# Board_ESP32_2Bluepill.net
KiCad netlist of a schematic drawn in EAGLE
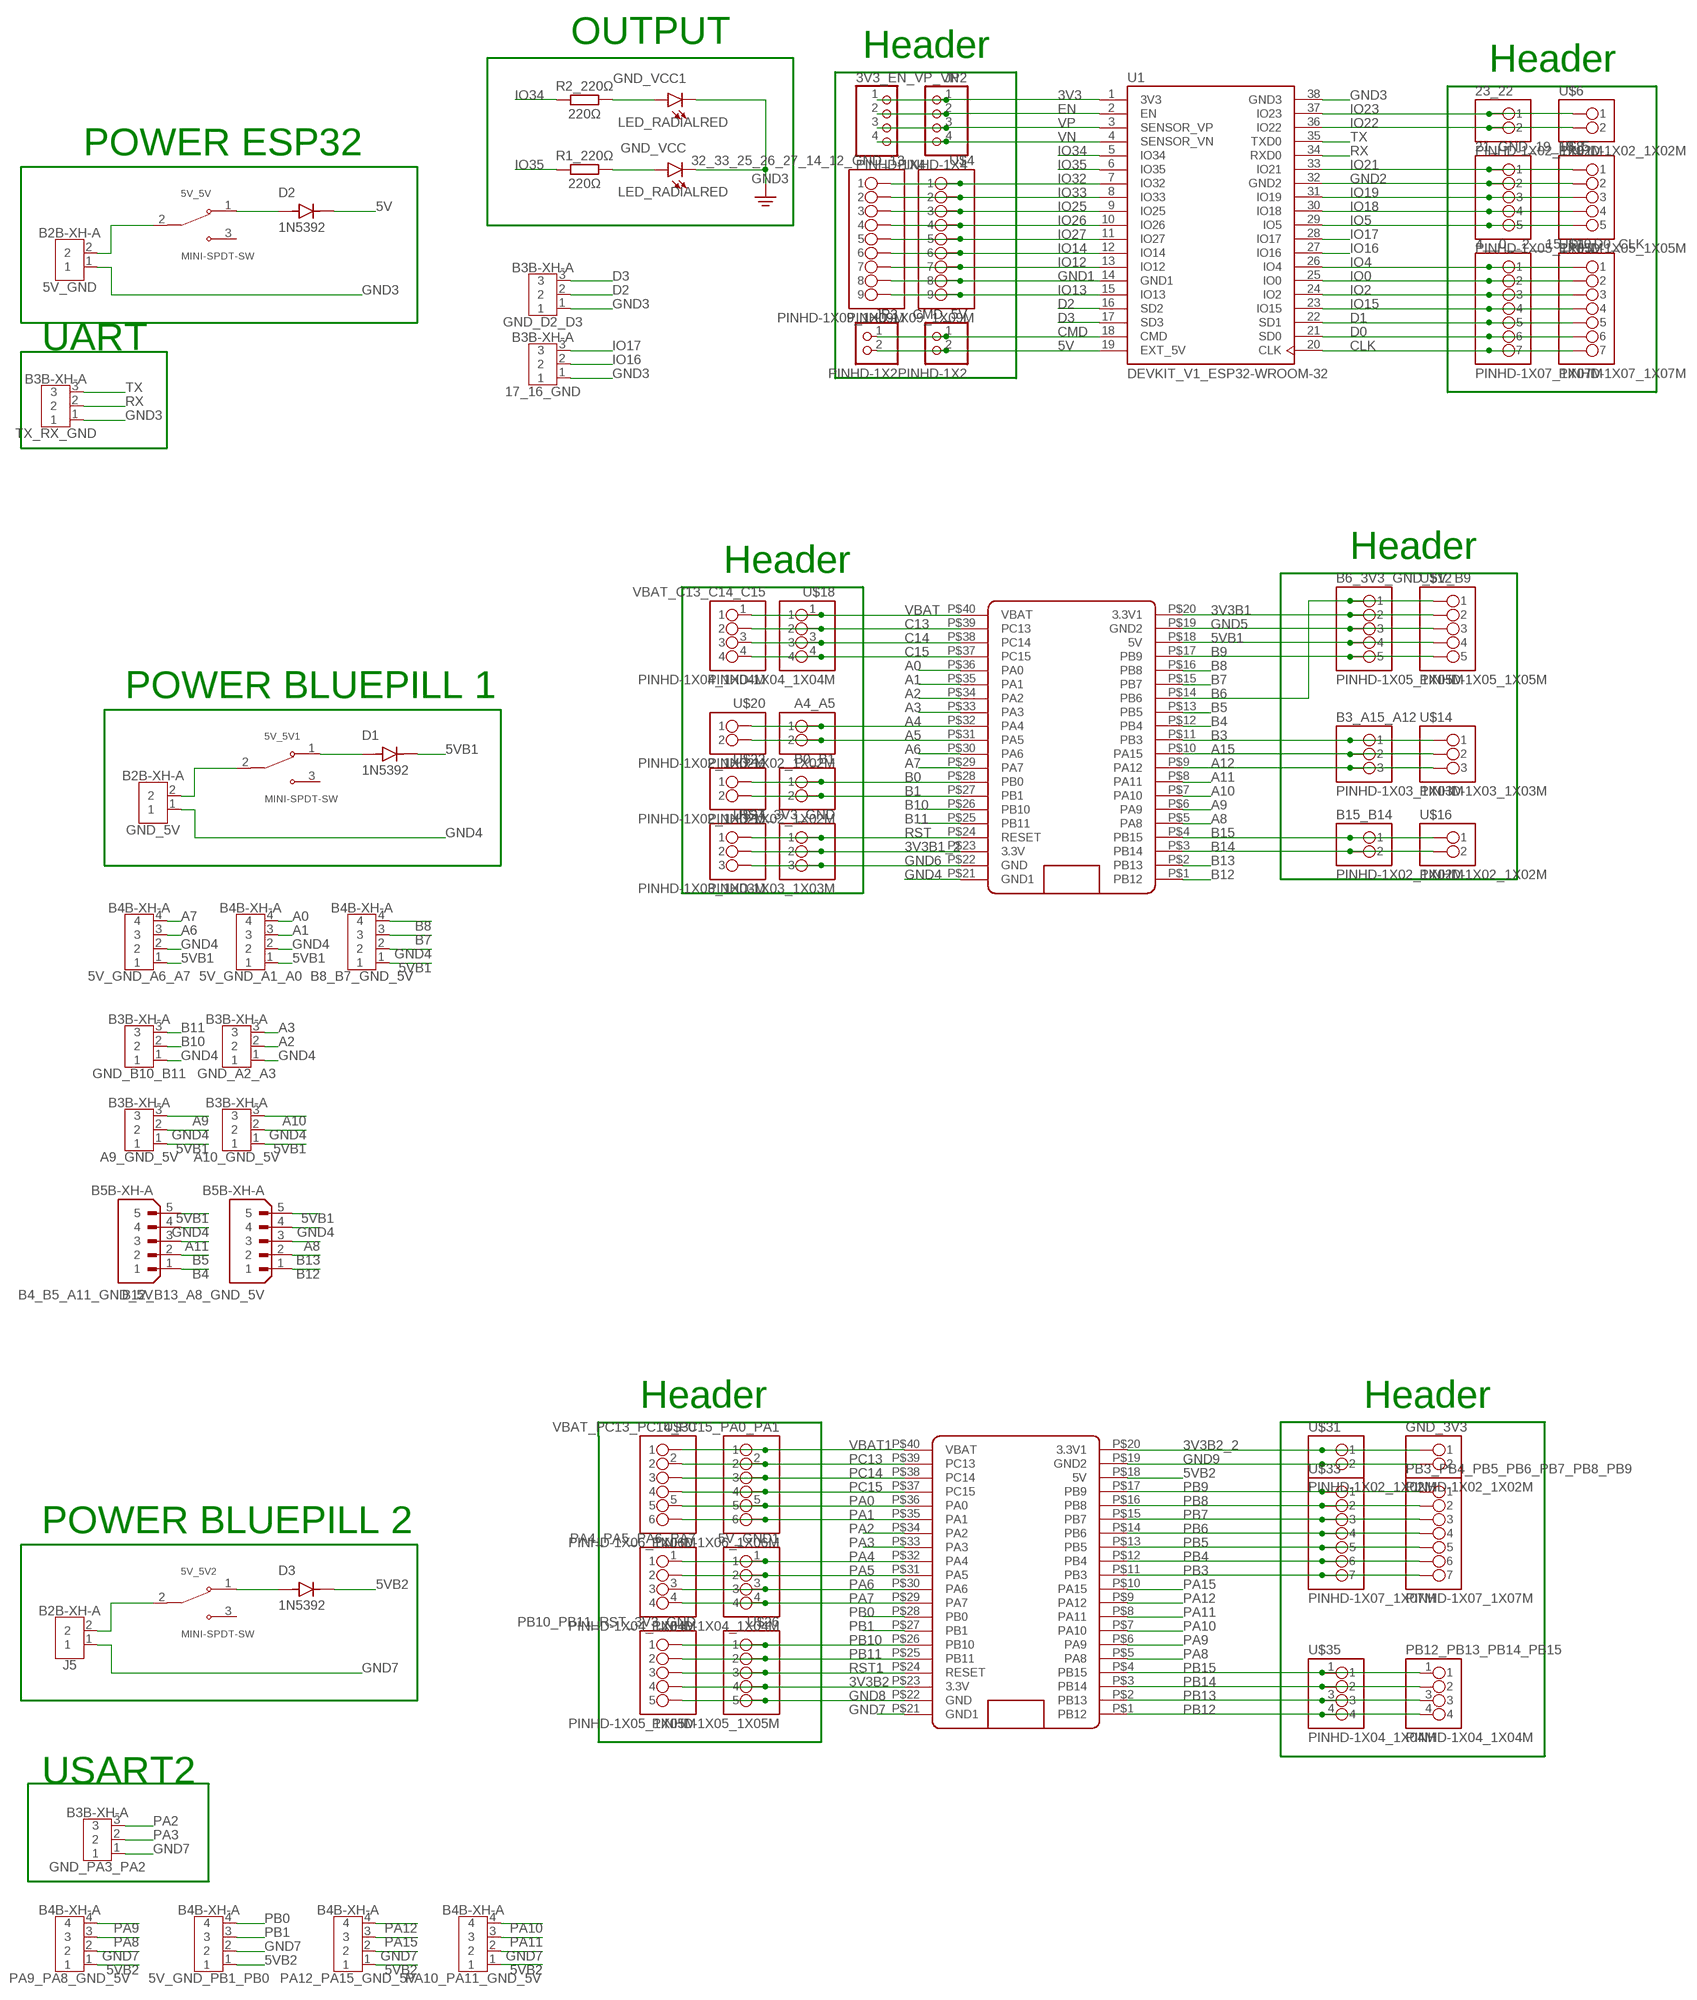
[diagram p0: schematic, sheet 1]

(export (version "E")
  (design (tool "Eeschema 10.0.6"))
  (components
    (comp (ref "3V3_EN_VP_VN")
      (value "PINHD-1X4")
      (footprint "eagle-import:1X04")
      (libsource (lib "eagle-import") (part "PINHD-1X4"))
    )
    (comp (ref "4__0__2__15_D1_D0_CLK")
      (value "PINHD-1X07_1X07M")
      (footprint "eagle-import:1X07")
      (libsource (lib "eagle-import") (part "PINHD-1X07_1X07M"))
    )
    (comp (ref "5V_5V")
      (value "MINI-SPDT-SW")
      (footprint "eagle-import:SW_MINI-SPDT-SW")
      (fields (field (name "MF") "Gravitech"))
      (libsource (lib "eagle-import") (part "MINI-SPDT-SW"))
    )
    (comp (ref "5V_5V1")
      (value "MINI-SPDT-SW")
      (footprint "eagle-import:SW_MINI-SPDT-SW")
      (fields (field (name "MF") "Gravitech"))
      (libsource (lib "eagle-import") (part "MINI-SPDT-SW"))
    )
    (comp (ref "5V_5V2")
      (value "MINI-SPDT-SW")
      (footprint "eagle-import:SW_MINI-SPDT-SW")
      (fields (field (name "MF") "Gravitech"))
      (libsource (lib "eagle-import") (part "MINI-SPDT-SW"))
    )
    (comp (ref "5V_GND")
      (value "B2B-XH-A")
      (footprint "eagle-import:B2B-XH-A")
      (fields (field (name "MANUFACTURER") "JST Sales America Inc."))
      (libsource (lib "eagle-import") (part "B2B-XH-A"))
    )
    (comp (ref "5V_GND1")
      (value "PINHD-1X04_1X04M")
      (footprint "eagle-import:1X04")
      (libsource (lib "eagle-import") (part "PINHD-1X04_1X04M"))
    )
    (comp (ref "5V_GND_A1_A0")
      (value "B4B-XH-A")
      (footprint "eagle-import:B4B-XH-A")
      (fields (field (name "MANUFACTURER") "JST Sales America Inc."))
      (libsource (lib "eagle-import") (part "B4B-XH-A"))
    )
    (comp (ref "5V_GND_A6_A7")
      (value "B4B-XH-A")
      (footprint "eagle-import:B4B-XH-A")
      (fields (field (name "MANUFACTURER") "JST Sales America Inc."))
      (libsource (lib "eagle-import") (part "B4B-XH-A"))
    )
    (comp (ref "5V_GND_PB1_PB0")
      (value "B4B-XH-A")
      (footprint "eagle-import:B4B-XH-A")
      (fields (field (name "MANUFACTURER") "JST Sales America Inc."))
      (libsource (lib "eagle-import") (part "B4B-XH-A"))
    )
    (comp (ref "17_16_GND")
      (value "B3B-XH-A")
      (footprint "eagle-import:B3B-XH-A")
      (fields (field (name "MANUFACTURER") "JST Sales America Inc."))
      (libsource (lib "eagle-import") (part "B3B-XH-A"))
    )
    (comp (ref "21_GND_19_18_5")
      (value "PINHD-1X05_1X05M")
      (footprint "eagle-import:1X05")
      (libsource (lib "eagle-import") (part "PINHD-1X05_1X05M"))
    )
    (comp (ref "23_22")
      (value "PINHD-1X02_1X02M")
      (footprint "eagle-import:1X02")
      (libsource (lib "eagle-import") (part "PINHD-1X02_1X02M"))
    )
    (comp (ref "32_33_25_26_27_14_12_GND_13")
      (value "PINHD-1X09_1X09M")
      (footprint "eagle-import:1X09")
      (libsource (lib "eagle-import") (part "PINHD-1X09_1X09M"))
    )
    (comp (ref "A4_A5")
      (value "PINHD-1X02_1X02M")
      (footprint "eagle-import:1X02")
      (libsource (lib "eagle-import") (part "PINHD-1X02_1X02M"))
    )
    (comp (ref "A9_GND_5V")
      (value "B3B-XH-A")
      (footprint "eagle-import:B3B-XH-A")
      (fields (field (name "MANUFACTURER") "JST Sales America Inc."))
      (libsource (lib "eagle-import") (part "B3B-XH-A"))
    )
    (comp (ref "A10_GND_5V")
      (value "B3B-XH-A")
      (footprint "eagle-import:B3B-XH-A")
      (fields (field (name "MANUFACTURER") "JST Sales America Inc."))
      (libsource (lib "eagle-import") (part "B3B-XH-A"))
    )
    (comp (ref "B0_B1")
      (value "PINHD-1X02_1X02M")
      (footprint "eagle-import:1X02")
      (libsource (lib "eagle-import") (part "PINHD-1X02_1X02M"))
    )
    (comp (ref "B3_A15_A12")
      (value "PINHD-1X03_1X03M")
      (footprint "eagle-import:1X03")
      (libsource (lib "eagle-import") (part "PINHD-1X03_1X03M"))
    )
    (comp (ref "B4_B5_A11_GND_5V")
      (value "B5B-XH-A")
      (footprint "eagle-import:JST_B5B-XH-A")
      (fields (field (name "MF") "JST Sales"))
      (libsource (lib "eagle-import") (part "B5B-XH-A"))
    )
    (comp (ref "B6_3V3_GND_5V_B9")
      (value "PINHD-1X05_1X05M")
      (footprint "eagle-import:1X05")
      (libsource (lib "eagle-import") (part "PINHD-1X05_1X05M"))
    )
    (comp (ref "B8_B7_GND_5V")
      (value "B4B-XH-A")
      (footprint "eagle-import:B4B-XH-A")
      (fields (field (name "MANUFACTURER") "JST Sales America Inc."))
      (libsource (lib "eagle-import") (part "B4B-XH-A"))
    )
    (comp (ref "B12_B13_A8_GND_5V")
      (value "B5B-XH-A")
      (footprint "eagle-import:JST_B5B-XH-A")
      (fields (field (name "MF") "JST Sales"))
      (libsource (lib "eagle-import") (part "B5B-XH-A"))
    )
    (comp (ref "B15_B14")
      (value "PINHD-1X02_1X02M")
      (footprint "eagle-import:1X02")
      (libsource (lib "eagle-import") (part "PINHD-1X02_1X02M"))
    )
    (comp (ref "CMD_5V")
      (value "PINHD-1X2")
      (footprint "eagle-import:1X02")
      (libsource (lib "eagle-import") (part "PINHD-1X2"))
    )
    (comp (ref "D1")
      (value "1N5392")
      (footprint "eagle-import:DIOAD1300W80L670D310")
      (fields (field (name "MF") "ON Semiconductor"))
      (libsource (lib "eagle-import") (part "1N5392"))
    )
    (comp (ref "D2")
      (value "1N5392")
      (footprint "eagle-import:DIOAD1300W80L670D310")
      (fields (field (name "MF") "ON Semiconductor"))
      (libsource (lib "eagle-import") (part "1N5392"))
    )
    (comp (ref "D3")
      (value "1N5392")
      (footprint "eagle-import:DIOAD1300W80L670D310")
      (fields (field (name "MF") "ON Semiconductor"))
      (libsource (lib "eagle-import") (part "1N5392"))
    )
    (comp (ref "GND_3V3")
      (value "PINHD-1X02_1X02M")
      (footprint "eagle-import:1X02")
      (libsource (lib "eagle-import") (part "PINHD-1X02_1X02M"))
    )
    (comp (ref "GND_5V")
      (value "B2B-XH-A")
      (footprint "eagle-import:B2B-XH-A")
      (fields (field (name "MANUFACTURER") "JST Sales America Inc."))
      (libsource (lib "eagle-import") (part "B2B-XH-A"))
    )
    (comp (ref "GND_A2_A3")
      (value "B3B-XH-A")
      (footprint "eagle-import:B3B-XH-A")
      (fields (field (name "MANUFACTURER") "JST Sales America Inc."))
      (libsource (lib "eagle-import") (part "B3B-XH-A"))
    )
    (comp (ref "GND_B10_B11")
      (value "B3B-XH-A")
      (footprint "eagle-import:B3B-XH-A")
      (fields (field (name "MANUFACTURER") "JST Sales America Inc."))
      (libsource (lib "eagle-import") (part "B3B-XH-A"))
    )
    (comp (ref "GND_D2_D3")
      (value "B3B-XH-A")
      (footprint "eagle-import:B3B-XH-A")
      (fields (field (name "MANUFACTURER") "JST Sales America Inc."))
      (libsource (lib "eagle-import") (part "B3B-XH-A"))
    )
    (comp (ref "GND_PA3_PA2")
      (value "B3B-XH-A")
      (footprint "eagle-import:B3B-XH-A")
      (fields (field (name "MANUFACTURER") "JST Sales America Inc."))
      (libsource (lib "eagle-import") (part "B3B-XH-A"))
    )
    (comp (ref "GND_VCC")
      (value "LED_RADIALRED")
      (footprint "eagle-import:LEDRD254W60D565H860B_R")
      (libsource (lib "eagle-import") (part "LED_RADIALRED"))
    )
    (comp (ref "GND_VCC1")
      (value "LED_RADIALRED")
      (footprint "eagle-import:LEDRD254W60D565H860B_R")
      (libsource (lib "eagle-import") (part "LED_RADIALRED"))
    )
    (comp (ref "J5")
      (value "B2B-XH-A")
      (footprint "eagle-import:B2B-XH-A")
      (fields (field (name "MANUFACTURER") "JST Sales America Inc."))
      (libsource (lib "eagle-import") (part "B2B-XH-A"))
    )
    (comp (ref "JP2")
      (value "PINHD-1X4")
      (footprint "eagle-import:1X04")
      (libsource (lib "eagle-import") (part "PINHD-1X4"))
    )
    (comp (ref "JP3")
      (value "PINHD-1X2")
      (footprint "eagle-import:1X02")
      (libsource (lib "eagle-import") (part "PINHD-1X2"))
    )
    (comp (ref "PA4_PA5_PA6_PA7")
      (value "PINHD-1X04_1X04M")
      (footprint "eagle-import:1X04")
      (libsource (lib "eagle-import") (part "PINHD-1X04_1X04M"))
    )
    (comp (ref "PA9_PA8_GND_5V")
      (value "B4B-XH-A")
      (footprint "eagle-import:B4B-XH-A")
      (fields (field (name "MANUFACTURER") "JST Sales America Inc."))
      (libsource (lib "eagle-import") (part "B4B-XH-A"))
    )
    (comp (ref "PA10_PA11_GND_5V")
      (value "B4B-XH-A")
      (footprint "eagle-import:B4B-XH-A")
      (fields (field (name "MANUFACTURER") "JST Sales America Inc."))
      (libsource (lib "eagle-import") (part "B4B-XH-A"))
    )
    (comp (ref "PA12_PA15_GND_5V")
      (value "B4B-XH-A")
      (footprint "eagle-import:B4B-XH-A")
      (fields (field (name "MANUFACTURER") "JST Sales America Inc."))
      (libsource (lib "eagle-import") (part "B4B-XH-A"))
    )
    (comp (ref "PB3_PB4_PB5_PB6_PB7_PB8_PB9")
      (value "PINHD-1X07_1X07M")
      (footprint "eagle-import:1X07")
      (libsource (lib "eagle-import") (part "PINHD-1X07_1X07M"))
    )
    (comp (ref "PB10_PB11_RST_3V3_GND")
      (value "PINHD-1X05_1X05M")
      (footprint "eagle-import:1X05")
      (libsource (lib "eagle-import") (part "PINHD-1X05_1X05M"))
    )
    (comp (ref "PB12_PB13_PB14_PB15")
      (value "PINHD-1X04_1X04M")
      (footprint "eagle-import:1X04")
      (libsource (lib "eagle-import") (part "PINHD-1X04_1X04M"))
    )
    (comp (ref "R1_220Ω")
      (value "220Ω")
      (footprint "eagle-import:RESAD1176W63L850D250B")
      (libsource (lib "eagle-import") (part "RAXIAL-11.7MM-PITCH_"))
    )
    (comp (ref "R2_220Ω")
      (value "220Ω")
      (footprint "eagle-import:RESAD1176W63L850D250B")
      (libsource (lib "eagle-import") (part "RAXIAL-11.7MM-PITCH_"))
    )
    (comp (ref "RST_3V3_GND")
      (value "PINHD-1X03_1X03M")
      (footprint "eagle-import:1X03")
      (libsource (lib "eagle-import") (part "PINHD-1X03_1X03M"))
    )
    (comp (ref "TX_RX_GND")
      (value "B3B-XH-A")
      (footprint "eagle-import:B3B-XH-A")
      (fields (field (name "MANUFACTURER") "JST Sales America Inc."))
      (libsource (lib "eagle-import") (part "B3B-XH-A"))
    )
    (comp (ref "U$1")
      (value "BLUE_PILL")
      (footprint "eagle-import:BLUE_PILL")
      (libsource (lib "eagle-import") (part "BLUE_PILL"))
    )
    (comp (ref "U$2")
      (value "BLUE_PILL")
      (footprint "eagle-import:BLUE_PILL")
      (libsource (lib "eagle-import") (part "BLUE_PILL"))
    )
    (comp (ref "U$4")
      (value "PINHD-1X09_1X09M")
      (footprint "eagle-import:1X09")
      (libsource (lib "eagle-import") (part "PINHD-1X09_1X09M"))
    )
    (comp (ref "U$6")
      (value "PINHD-1X02_1X02M")
      (footprint "eagle-import:1X02")
      (libsource (lib "eagle-import") (part "PINHD-1X02_1X02M"))
    )
    (comp (ref "U$8")
      (value "PINHD-1X05_1X05M")
      (footprint "eagle-import:1X05")
      (libsource (lib "eagle-import") (part "PINHD-1X05_1X05M"))
    )
    (comp (ref "U$10")
      (value "PINHD-1X07_1X07M")
      (footprint "eagle-import:1X07")
      (libsource (lib "eagle-import") (part "PINHD-1X07_1X07M"))
    )
    (comp (ref "U$12")
      (value "PINHD-1X05_1X05M")
      (footprint "eagle-import:1X05")
      (libsource (lib "eagle-import") (part "PINHD-1X05_1X05M"))
    )
    (comp (ref "U$14")
      (value "PINHD-1X03_1X03M")
      (footprint "eagle-import:1X03")
      (libsource (lib "eagle-import") (part "PINHD-1X03_1X03M"))
    )
    (comp (ref "U$16")
      (value "PINHD-1X02_1X02M")
      (footprint "eagle-import:1X02")
      (libsource (lib "eagle-import") (part "PINHD-1X02_1X02M"))
    )
    (comp (ref "U$18")
      (value "PINHD-1X04_1X04M")
      (footprint "eagle-import:1X04")
      (libsource (lib "eagle-import") (part "PINHD-1X04_1X04M"))
    )
    (comp (ref "U$20")
      (value "PINHD-1X02_1X02M")
      (footprint "eagle-import:1X02")
      (libsource (lib "eagle-import") (part "PINHD-1X02_1X02M"))
    )
    (comp (ref "U$22")
      (value "PINHD-1X02_1X02M")
      (footprint "eagle-import:1X02")
      (libsource (lib "eagle-import") (part "PINHD-1X02_1X02M"))
    )
    (comp (ref "U$24")
      (value "PINHD-1X03_1X03M")
      (footprint "eagle-import:1X03")
      (libsource (lib "eagle-import") (part "PINHD-1X03_1X03M"))
    )
    (comp (ref "U$26")
      (value "PINHD-1X05_1X05M")
      (footprint "eagle-import:1X05")
      (libsource (lib "eagle-import") (part "PINHD-1X05_1X05M"))
    )
    (comp (ref "U$30")
      (value "PINHD-1X06_1X06M")
      (footprint "eagle-import:1X06")
      (libsource (lib "eagle-import") (part "PINHD-1X06_1X06M"))
    )
    (comp (ref "U$31")
      (value "PINHD-1X02_1X02M")
      (footprint "eagle-import:1X02")
      (libsource (lib "eagle-import") (part "PINHD-1X02_1X02M"))
    )
    (comp (ref "U$33")
      (value "PINHD-1X07_1X07M")
      (footprint "eagle-import:1X07")
      (libsource (lib "eagle-import") (part "PINHD-1X07_1X07M"))
    )
    (comp (ref "U$35")
      (value "PINHD-1X04_1X04M")
      (footprint "eagle-import:1X04")
      (libsource (lib "eagle-import") (part "PINHD-1X04_1X04M"))
    )
    (comp (ref "U1")
      (value "DEVKIT_V1_ESP32-WROOM-32")
      (footprint "eagle-import:MODULE_DEVKIT_V1_ESP32-WROOM-32")
      (fields (field (name "MF") "Espressif Systems") (field (name "MP") "DEVKIT V1 ESP32-WROOM-32"))
      (libsource (lib "eagle-import") (part "DEVKIT_V1_ESP32-WROOM-32"))
    )
    (comp (ref "VBAT_C13_C14_C15")
      (value "PINHD-1X04_1X04M")
      (footprint "eagle-import:1X04")
      (libsource (lib "eagle-import") (part "PINHD-1X04_1X04M"))
    )
    (comp (ref "VBAT_PC13_PC14_PC15_PA0_PA1")
      (value "PINHD-1X06_1X06M")
      (footprint "eagle-import:1X06")
      (libsource (lib "eagle-import") (part "PINHD-1X06_1X06M"))
    )
  )
  (nets
    (net (code "1") (name "/3V3") (class "Default")
      (node (ref "3V3_EN_VP_VN") (pin "1") (pinfunction "1_1") (pintype "passive"))
      (node (ref "JP2") (pin "1") (pinfunction "1_1") (pintype "passive"))
      (node (ref "U1") (pin "1") (pinfunction "3V3_1") (pintype "power_in"))
    )
    (net (code "2") (name "/3V3B1") (class "Default")
      (node (ref "B6_3V3_GND_5V_B9") (pin "2") (pinfunction "2_2") (pintype "bidirectional"))
      (node (ref "U$1") (pin "P$20") (pinfunction "3.3V1_P$20") (pintype "bidirectional"))
      (node (ref "U$12") (pin "2") (pinfunction "2_2") (pintype "bidirectional"))
    )
    (net (code "3") (name "/3V3B1_2") (class "Default")
      (node (ref "RST_3V3_GND") (pin "2") (pinfunction "2_2") (pintype "bidirectional"))
      (node (ref "U$1") (pin "P$23") (pinfunction "3.3V_P$23") (pintype "bidirectional"))
      (node (ref "U$24") (pin "2") (pinfunction "2_2") (pintype "bidirectional"))
    )
    (net (code "4") (name "/3V3B2") (class "Default")
      (node (ref "PB10_PB11_RST_3V3_GND") (pin "4") (pinfunction "4_4") (pintype "bidirectional"))
      (node (ref "U$2") (pin "P$23") (pinfunction "3.3V_P$23") (pintype "bidirectional"))
      (node (ref "U$26") (pin "4") (pinfunction "4_4") (pintype "bidirectional"))
    )
    (net (code "5") (name "/3V3B2_2") (class "Default")
      (node (ref "GND_3V3") (pin "1") (pinfunction "1_1") (pintype "bidirectional"))
      (node (ref "U$2") (pin "P$20") (pinfunction "3.3V1_P$20") (pintype "bidirectional"))
      (node (ref "U$31") (pin "1") (pinfunction "1_1") (pintype "bidirectional"))
    )
    (net (code "6") (name "/5V") (class "Default")
      (node (ref "CMD_5V") (pin "2") (pinfunction "2_2") (pintype "passive"))
      (node (ref "D2") (pin "C") (pinfunction "K_C") (pintype "passive"))
      (node (ref "JP3") (pin "2") (pinfunction "2_2") (pintype "passive"))
      (node (ref "U1") (pin "19") (pinfunction "EXT_5V_19") (pintype "power_in"))
    )
    (net (code "7") (name "/5VB1") (class "Default")
      (node (ref "5V_GND_A1_A0") (pin "1") (pinfunction "1_1") (pintype "bidirectional"))
      (node (ref "5V_GND_A6_A7") (pin "1") (pinfunction "1_1") (pintype "bidirectional"))
      (node (ref "A10_GND_5V") (pin "1") (pinfunction "1_1") (pintype "bidirectional"))
      (node (ref "A9_GND_5V") (pin "1") (pinfunction "1_1") (pintype "bidirectional"))
      (node (ref "B12_B13_A8_GND_5V") (pin "5") (pinfunction "5_5") (pintype "passive"))
      (node (ref "B4_B5_A11_GND_5V") (pin "5") (pinfunction "5_5") (pintype "passive"))
      (node (ref "B6_3V3_GND_5V_B9") (pin "4") (pinfunction "4_4") (pintype "bidirectional"))
      (node (ref "B8_B7_GND_5V") (pin "1") (pinfunction "1_1") (pintype "bidirectional"))
      (node (ref "D1") (pin "C") (pinfunction "K_C") (pintype "passive"))
      (node (ref "U$1") (pin "P$18") (pinfunction "5V_P$18") (pintype "bidirectional"))
      (node (ref "U$12") (pin "4") (pinfunction "4_4") (pintype "bidirectional"))
    )
    (net (code "8") (name "/5VB2") (class "Default")
      (node (ref "5V_GND_PB1_PB0") (pin "1") (pinfunction "1_1") (pintype "bidirectional"))
      (node (ref "D3") (pin "C") (pinfunction "K_C") (pintype "passive"))
      (node (ref "PA10_PA11_GND_5V") (pin "1") (pinfunction "1_1") (pintype "bidirectional"))
      (node (ref "PA12_PA15_GND_5V") (pin "1") (pinfunction "1_1") (pintype "bidirectional"))
      (node (ref "PA9_PA8_GND_5V") (pin "1") (pinfunction "1_1") (pintype "bidirectional"))
      (node (ref "U$2") (pin "P$18") (pinfunction "5V_P$18") (pintype "bidirectional"))
    )
    (net (code "9") (name "/A0") (class "Default")
      (node (ref "5V_GND_A1_A0") (pin "4") (pinfunction "4_4") (pintype "bidirectional"))
      (node (ref "U$1") (pin "P$36") (pinfunction "PA0_P$36") (pintype "bidirectional"))
    )
    (net (code "10") (name "/A1") (class "Default")
      (node (ref "5V_GND_A1_A0") (pin "3") (pinfunction "3_3") (pintype "bidirectional"))
      (node (ref "U$1") (pin "P$35") (pinfunction "PA1_P$35") (pintype "bidirectional"))
    )
    (net (code "11") (name "/A2") (class "Default")
      (node (ref "GND_A2_A3") (pin "2") (pinfunction "2_2") (pintype "bidirectional"))
      (node (ref "U$1") (pin "P$34") (pinfunction "PA2_P$34") (pintype "bidirectional"))
    )
    (net (code "12") (name "/A3") (class "Default")
      (node (ref "GND_A2_A3") (pin "3") (pinfunction "3_3") (pintype "bidirectional"))
      (node (ref "U$1") (pin "P$33") (pinfunction "PA3_P$33") (pintype "bidirectional"))
    )
    (net (code "13") (name "/A4") (class "Default")
      (node (ref "A4_A5") (pin "1") (pinfunction "1_1") (pintype "bidirectional"))
      (node (ref "U$1") (pin "P$32") (pinfunction "PA4_P$32") (pintype "bidirectional"))
      (node (ref "U$20") (pin "1") (pinfunction "1_1") (pintype "bidirectional"))
    )
    (net (code "14") (name "/A5") (class "Default")
      (node (ref "A4_A5") (pin "2") (pinfunction "2_2") (pintype "bidirectional"))
      (node (ref "U$1") (pin "P$31") (pinfunction "PA5_P$31") (pintype "bidirectional"))
      (node (ref "U$20") (pin "2") (pinfunction "2_2") (pintype "bidirectional"))
    )
    (net (code "15") (name "/A6") (class "Default")
      (node (ref "5V_GND_A6_A7") (pin "3") (pinfunction "3_3") (pintype "bidirectional"))
      (node (ref "U$1") (pin "P$30") (pinfunction "PA6_P$30") (pintype "bidirectional"))
    )
    (net (code "16") (name "/A7") (class "Default")
      (node (ref "5V_GND_A6_A7") (pin "4") (pinfunction "4_4") (pintype "bidirectional"))
      (node (ref "U$1") (pin "P$29") (pinfunction "PA7_P$29") (pintype "bidirectional"))
    )
    (net (code "17") (name "/A8") (class "Default")
      (node (ref "B12_B13_A8_GND_5V") (pin "3") (pinfunction "3_3") (pintype "passive"))
      (node (ref "U$1") (pin "P$5") (pinfunction "PA8_P$5") (pintype "bidirectional"))
    )
    (net (code "18") (name "/A9") (class "Default")
      (node (ref "A9_GND_5V") (pin "3") (pinfunction "3_3") (pintype "bidirectional"))
      (node (ref "U$1") (pin "P$6") (pinfunction "PA9_P$6") (pintype "bidirectional"))
    )
    (net (code "19") (name "/A10") (class "Default")
      (node (ref "A10_GND_5V") (pin "3") (pinfunction "3_3") (pintype "bidirectional"))
      (node (ref "U$1") (pin "P$7") (pinfunction "PA10_P$7") (pintype "bidirectional"))
    )
    (net (code "20") (name "/A11") (class "Default")
      (node (ref "B4_B5_A11_GND_5V") (pin "3") (pinfunction "3_3") (pintype "passive"))
      (node (ref "U$1") (pin "P$8") (pinfunction "PA11_P$8") (pintype "bidirectional"))
    )
    (net (code "21") (name "/A12") (class "Default")
      (node (ref "B3_A15_A12") (pin "3") (pinfunction "3_3") (pintype "bidirectional"))
      (node (ref "U$1") (pin "P$9") (pinfunction "PA12_P$9") (pintype "bidirectional"))
      (node (ref "U$14") (pin "3") (pinfunction "3_3") (pintype "bidirectional"))
    )
    (net (code "22") (name "/A15") (class "Default")
      (node (ref "B3_A15_A12") (pin "2") (pinfunction "2_2") (pintype "bidirectional"))
      (node (ref "U$1") (pin "P$10") (pinfunction "PA15_P$10") (pintype "bidirectional"))
      (node (ref "U$14") (pin "2") (pinfunction "2_2") (pintype "bidirectional"))
    )
    (net (code "23") (name "/B0") (class "Default")
      (node (ref "B0_B1") (pin "1") (pinfunction "1_1") (pintype "bidirectional"))
      (node (ref "U$1") (pin "P$28") (pinfunction "PB0_P$28") (pintype "bidirectional"))
      (node (ref "U$22") (pin "1") (pinfunction "1_1") (pintype "bidirectional"))
    )
    (net (code "24") (name "/B1") (class "Default")
      (node (ref "B0_B1") (pin "2") (pinfunction "2_2") (pintype "bidirectional"))
      (node (ref "U$1") (pin "P$27") (pinfunction "PB1_P$27") (pintype "bidirectional"))
      (node (ref "U$22") (pin "2") (pinfunction "2_2") (pintype "bidirectional"))
    )
    (net (code "25") (name "/B3") (class "Default")
      (node (ref "B3_A15_A12") (pin "1") (pinfunction "1_1") (pintype "bidirectional"))
      (node (ref "U$1") (pin "P$11") (pinfunction "PB3_P$11") (pintype "bidirectional"))
      (node (ref "U$14") (pin "1") (pinfunction "1_1") (pintype "bidirectional"))
    )
    (net (code "26") (name "/B4") (class "Default")
      (node (ref "B4_B5_A11_GND_5V") (pin "1") (pinfunction "1_1") (pintype "passive"))
      (node (ref "U$1") (pin "P$12") (pinfunction "PB4_P$12") (pintype "bidirectional"))
    )
    (net (code "27") (name "/B5") (class "Default")
      (node (ref "B4_B5_A11_GND_5V") (pin "2") (pinfunction "2_2") (pintype "passive"))
      (node (ref "U$1") (pin "P$13") (pinfunction "PB5_P$13") (pintype "bidirectional"))
    )
    (net (code "28") (name "/B6") (class "Default")
      (node (ref "B6_3V3_GND_5V_B9") (pin "1") (pinfunction "1_1") (pintype "bidirectional"))
      (node (ref "U$1") (pin "P$14") (pinfunction "PB6_P$14") (pintype "bidirectional"))
      (node (ref "U$12") (pin "1") (pinfunction "1_1") (pintype "bidirectional"))
    )
    (net (code "29") (name "/B7") (class "Default")
      (node (ref "B8_B7_GND_5V") (pin "3") (pinfunction "3_3") (pintype "bidirectional"))
      (node (ref "U$1") (pin "P$15") (pinfunction "PB7_P$15") (pintype "bidirectional"))
    )
    (net (code "30") (name "/B8") (class "Default")
      (node (ref "B8_B7_GND_5V") (pin "4") (pinfunction "4_4") (pintype "bidirectional"))
      (node (ref "U$1") (pin "P$16") (pinfunction "PB8_P$16") (pintype "bidirectional"))
    )
    (net (code "31") (name "/B9") (class "Default")
      (node (ref "B6_3V3_GND_5V_B9") (pin "5") (pinfunction "5_5") (pintype "bidirectional"))
      (node (ref "U$1") (pin "P$17") (pinfunction "PB9_P$17") (pintype "bidirectional"))
      (node (ref "U$12") (pin "5") (pinfunction "5_5") (pintype "bidirectional"))
    )
    (net (code "32") (name "/B10") (class "Default")
      (node (ref "GND_B10_B11") (pin "2") (pinfunction "2_2") (pintype "bidirectional"))
      (node (ref "U$1") (pin "P$26") (pinfunction "PB10_P$26") (pintype "bidirectional"))
    )
    (net (code "33") (name "/B11") (class "Default")
      (node (ref "GND_B10_B11") (pin "3") (pinfunction "3_3") (pintype "bidirectional"))
      (node (ref "U$1") (pin "P$25") (pinfunction "PB11_P$25") (pintype "bidirectional"))
    )
    (net (code "34") (name "/B12") (class "Default")
      (node (ref "B12_B13_A8_GND_5V") (pin "1") (pinfunction "1_1") (pintype "passive"))
      (node (ref "U$1") (pin "P$1") (pinfunction "PB12_P$1") (pintype "bidirectional"))
    )
    (net (code "35") (name "/B13") (class "Default")
      (node (ref "B12_B13_A8_GND_5V") (pin "2") (pinfunction "2_2") (pintype "passive"))
      (node (ref "U$1") (pin "P$2") (pinfunction "PB13_P$2") (pintype "bidirectional"))
    )
    (net (code "36") (name "/B14") (class "Default")
      (node (ref "B15_B14") (pin "2") (pinfunction "2_2") (pintype "bidirectional"))
      (node (ref "U$1") (pin "P$3") (pinfunction "PB14_P$3") (pintype "bidirectional"))
      (node (ref "U$16") (pin "2") (pinfunction "2_2") (pintype "bidirectional"))
    )
    (net (code "37") (name "/B15") (class "Default")
      (node (ref "B15_B14") (pin "1") (pinfunction "1_1") (pintype "bidirectional"))
      (node (ref "U$1") (pin "P$4") (pinfunction "PB15_P$4") (pintype "bidirectional"))
      (node (ref "U$16") (pin "1") (pinfunction "1_1") (pintype "bidirectional"))
    )
    (net (code "38") (name "/C13") (class "Default")
      (node (ref "U$1") (pin "P$39") (pinfunction "PC13_P$39") (pintype "bidirectional"))
      (node (ref "U$18") (pin "2") (pinfunction "2_2") (pintype "bidirectional"))
      (node (ref "VBAT_C13_C14_C15") (pin "2") (pinfunction "2_2") (pintype "bidirectional"))
    )
    (net (code "39") (name "/C14") (class "Default")
      (node (ref "U$1") (pin "P$38") (pinfunction "PC14_P$38") (pintype "bidirectional"))
      (node (ref "U$18") (pin "3") (pinfunction "3_3") (pintype "bidirectional"))
      (node (ref "VBAT_C13_C14_C15") (pin "3") (pinfunction "3_3") (pintype "bidirectional"))
    )
    (net (code "40") (name "/C15") (class "Default")
      (node (ref "U$1") (pin "P$37") (pinfunction "PC15_P$37") (pintype "bidirectional"))
      (node (ref "U$18") (pin "4") (pinfunction "4_4") (pintype "bidirectional"))
      (node (ref "VBAT_C13_C14_C15") (pin "4") (pinfunction "4_4") (pintype "bidirectional"))
    )
    (net (code "41") (name "/CLK") (class "Default")
      (node (ref "4__0__2__15_D1_D0_CLK") (pin "7") (pinfunction "7_7") (pintype "bidirectional"))
      (node (ref "U$10") (pin "7") (pinfunction "7_7") (pintype "bidirectional"))
      (node (ref "U1") (pin "20") (pinfunction "CLK_20") (pintype "input"))
    )
    (net (code "42") (name "/CMD") (class "Default")
      (node (ref "CMD_5V") (pin "1") (pinfunction "1_1") (pintype "passive"))
      (node (ref "JP3") (pin "1") (pinfunction "1_1") (pintype "passive"))
      (node (ref "U1") (pin "18") (pinfunction "CMD_18") (pintype "bidirectional"))
    )
    (net (code "43") (name "/D0") (class "Default")
      (node (ref "4__0__2__15_D1_D0_CLK") (pin "6") (pinfunction "6_6") (pintype "bidirectional"))
      (node (ref "U$10") (pin "6") (pinfunction "6_6") (pintype "bidirectional"))
      (node (ref "U1") (pin "21") (pinfunction "SD0_21") (pintype "bidirectional"))
    )
    (net (code "44") (name "/D1") (class "Default")
      (node (ref "4__0__2__15_D1_D0_CLK") (pin "5") (pinfunction "5_5") (pintype "bidirectional"))
      (node (ref "U$10") (pin "5") (pinfunction "5_5") (pintype "bidirectional"))
      (node (ref "U1") (pin "22") (pinfunction "SD1_22") (pintype "bidirectional"))
    )
    (net (code "45") (name "/D2") (class "Default")
      (node (ref "GND_D2_D3") (pin "2") (pinfunction "2_2") (pintype "bidirectional"))
      (node (ref "U1") (pin "16") (pinfunction "SD2_16") (pintype "bidirectional"))
    )
    (net (code "46") (name "/D3") (class "Default")
      (node (ref "GND_D2_D3") (pin "3") (pinfunction "3_3") (pintype "bidirectional"))
      (node (ref "U1") (pin "17") (pinfunction "SD3_17") (pintype "bidirectional"))
    )
    (net (code "47") (name "/EN") (class "Default")
      (node (ref "3V3_EN_VP_VN") (pin "2") (pinfunction "2_2") (pintype "passive"))
      (node (ref "JP2") (pin "2") (pinfunction "2_2") (pintype "passive"))
      (node (ref "U1") (pin "2") (pinfunction "EN_2") (pintype "input"))
    )
    (net (code "48") (name "/GND1") (class "Default")
      (node (ref "32_33_25_26_27_14_12_GND_13") (pin "8") (pinfunction "8_8") (pintype "bidirectional"))
      (node (ref "U$4") (pin "8") (pinfunction "8_8") (pintype "bidirectional"))
      (node (ref "U1") (pin "14") (pinfunction "GND1_14") (pintype "power_in"))
    )
    (net (code "49") (name "/GND2") (class "Default")
      (node (ref "21_GND_19_18_5") (pin "2") (pinfunction "2_2") (pintype "bidirectional"))
      (node (ref "U$8") (pin "2") (pinfunction "2_2") (pintype "bidirectional"))
      (node (ref "U1") (pin "32") (pinfunction "GND2_32") (pintype "power_in"))
    )
    (net (code "50") (name "/GND4") (class "Default")
      (node (ref "5V_GND_A1_A0") (pin "2") (pinfunction "2_2") (pintype "bidirectional"))
      (node (ref "5V_GND_A6_A7") (pin "2") (pinfunction "2_2") (pintype "bidirectional"))
      (node (ref "A10_GND_5V") (pin "2") (pinfunction "2_2") (pintype "bidirectional"))
      (node (ref "A9_GND_5V") (pin "2") (pinfunction "2_2") (pintype "bidirectional"))
      (node (ref "B12_B13_A8_GND_5V") (pin "4") (pinfunction "4_4") (pintype "passive"))
      (node (ref "B4_B5_A11_GND_5V") (pin "4") (pinfunction "4_4") (pintype "passive"))
      (node (ref "B8_B7_GND_5V") (pin "2") (pinfunction "2_2") (pintype "bidirectional"))
      (node (ref "GND_5V") (pin "1") (pinfunction "1_1") (pintype "bidirectional"))
      (node (ref "GND_A2_A3") (pin "1") (pinfunction "1_1") (pintype "bidirectional"))
      (node (ref "GND_B10_B11") (pin "1") (pinfunction "1_1") (pintype "bidirectional"))
      (node (ref "U$1") (pin "P$21") (pinfunction "GND1_P$21") (pintype "power_in"))
    )
    (net (code "51") (name "/GND5") (class "Default")
      (node (ref "B6_3V3_GND_5V_B9") (pin "3") (pinfunction "3_3") (pintype "bidirectional"))
      (node (ref "U$1") (pin "P$19") (pinfunction "GND2_P$19") (pintype "bidirectional"))
      (node (ref "U$12") (pin "3") (pinfunction "3_3") (pintype "bidirectional"))
    )
    (net (code "52") (name "/GND6") (class "Default")
      (node (ref "RST_3V3_GND") (pin "3") (pinfunction "3_3") (pintype "bidirectional"))
      (node (ref "U$1") (pin "P$22") (pinfunction "GND_P$22") (pintype "bidirectional"))
      (node (ref "U$24") (pin "3") (pinfunction "3_3") (pintype "bidirectional"))
    )
    (net (code "53") (name "/GND7") (class "Default")
      (node (ref "5V_GND_PB1_PB0") (pin "2") (pinfunction "2_2") (pintype "bidirectional"))
      (node (ref "GND_PA3_PA2") (pin "1") (pinfunction "1_1") (pintype "bidirectional"))
      (node (ref "J5") (pin "1") (pinfunction "1_1") (pintype "bidirectional"))
      (node (ref "PA10_PA11_GND_5V") (pin "2") (pinfunction "2_2") (pintype "bidirectional"))
      (node (ref "PA12_PA15_GND_5V") (pin "2") (pinfunction "2_2") (pintype "bidirectional"))
      (node (ref "PA9_PA8_GND_5V") (pin "2") (pinfunction "2_2") (pintype "bidirectional"))
      (node (ref "U$2") (pin "P$21") (pinfunction "GND1_P$21") (pintype "power_in"))
    )
    (net (code "54") (name "/GND8") (class "Default")
      (node (ref "PB10_PB11_RST_3V3_GND") (pin "5") (pinfunction "5_5") (pintype "bidirectional"))
      (node (ref "U$2") (pin "P$22") (pinfunction "GND_P$22") (pintype "bidirectional"))
      (node (ref "U$26") (pin "5") (pinfunction "5_5") (pintype "bidirectional"))
    )
    (net (code "55") (name "/GND9") (class "Default")
      (node (ref "GND_3V3") (pin "2") (pinfunction "2_2") (pintype "bidirectional"))
      (node (ref "U$2") (pin "P$19") (pinfunction "GND2_P$19") (pintype "bidirectional"))
      (node (ref "U$31") (pin "2") (pinfunction "2_2") (pintype "bidirectional"))
    )
    (net (code "56") (name "/IO0") (class "Default")
      (node (ref "4__0__2__15_D1_D0_CLK") (pin "2") (pinfunction "2_2") (pintype "bidirectional"))
      (node (ref "U$10") (pin "2") (pinfunction "2_2") (pintype "bidirectional"))
      (node (ref "U1") (pin "25") (pinfunction "IO0_25") (pintype "bidirectional"))
    )
    (net (code "57") (name "/IO2") (class "Default")
      (node (ref "4__0__2__15_D1_D0_CLK") (pin "3") (pinfunction "3_3") (pintype "bidirectional"))
      (node (ref "U$10") (pin "3") (pinfunction "3_3") (pintype "bidirectional"))
      (node (ref "U1") (pin "24") (pinfunction "IO2_24") (pintype "bidirectional"))
    )
    (net (code "58") (name "/IO4") (class "Default")
      (node (ref "4__0__2__15_D1_D0_CLK") (pin "1") (pinfunction "1_1") (pintype "bidirectional"))
      (node (ref "U$10") (pin "1") (pinfunction "1_1") (pintype "bidirectional"))
      (node (ref "U1") (pin "26") (pinfunction "IO4_26") (pintype "bidirectional"))
    )
    (net (code "59") (name "/IO5") (class "Default")
      (node (ref "21_GND_19_18_5") (pin "5") (pinfunction "5_5") (pintype "bidirectional"))
      (node (ref "U$8") (pin "5") (pinfunction "5_5") (pintype "bidirectional"))
      (node (ref "U1") (pin "29") (pinfunction "IO5_29") (pintype "bidirectional"))
    )
    (net (code "60") (name "/IO12") (class "Default")
      (node (ref "32_33_25_26_27_14_12_GND_13") (pin "7") (pinfunction "7_7") (pintype "bidirectional"))
      (node (ref "U$4") (pin "7") (pinfunction "7_7") (pintype "bidirectional"))
      (node (ref "U1") (pin "13") (pinfunction "IO12_13") (pintype "bidirectional"))
    )
    (net (code "61") (name "/IO13") (class "Default")
      (node (ref "32_33_25_26_27_14_12_GND_13") (pin "9") (pinfunction "9_9") (pintype "bidirectional"))
      (node (ref "U$4") (pin "9") (pinfunction "9_9") (pintype "bidirectional"))
      (node (ref "U1") (pin "15") (pinfunction "IO13_15") (pintype "bidirectional"))
    )
    (net (code "62") (name "/IO14") (class "Default")
      (node (ref "32_33_25_26_27_14_12_GND_13") (pin "6") (pinfunction "6_6") (pintype "bidirectional"))
      (node (ref "U$4") (pin "6") (pinfunction "6_6") (pintype "bidirectional"))
      (node (ref "U1") (pin "12") (pinfunction "IO14_12") (pintype "bidirectional"))
    )
    (net (code "63") (name "/IO15") (class "Default")
      (node (ref "4__0__2__15_D1_D0_CLK") (pin "4") (pinfunction "4_4") (pintype "bidirectional"))
      (node (ref "U$10") (pin "4") (pinfunction "4_4") (pintype "bidirectional"))
      (node (ref "U1") (pin "23") (pinfunction "IO15_23") (pintype "bidirectional"))
    )
    (net (code "64") (name "/IO16") (class "Default")
      (node (ref "17_16_GND") (pin "2") (pinfunction "2_2") (pintype "bidirectional"))
      (node (ref "U1") (pin "27") (pinfunction "IO16_27") (pintype "bidirectional"))
    )
    (net (code "65") (name "/IO17") (class "Default")
      (node (ref "17_16_GND") (pin "3") (pinfunction "3_3") (pintype "bidirectional"))
      (node (ref "U1") (pin "28") (pinfunction "IO17_28") (pintype "bidirectional"))
    )
    (net (code "66") (name "/IO18") (class "Default")
      (node (ref "21_GND_19_18_5") (pin "4") (pinfunction "4_4") (pintype "bidirectional"))
      (node (ref "U$8") (pin "4") (pinfunction "4_4") (pintype "bidirectional"))
      (node (ref "U1") (pin "30") (pinfunction "IO18_30") (pintype "bidirectional"))
    )
    (net (code "67") (name "/IO19") (class "Default")
      (node (ref "21_GND_19_18_5") (pin "3") (pinfunction "3_3") (pintype "bidirectional"))
      (node (ref "U$8") (pin "3") (pinfunction "3_3") (pintype "bidirectional"))
      (node (ref "U1") (pin "31") (pinfunction "IO19_31") (pintype "bidirectional"))
    )
    (net (code "68") (name "/IO21") (class "Default")
      (node (ref "21_GND_19_18_5") (pin "1") (pinfunction "1_1") (pintype "bidirectional"))
      (node (ref "U$8") (pin "1") (pinfunction "1_1") (pintype "bidirectional"))
      (node (ref "U1") (pin "33") (pinfunction "IO21_33") (pintype "bidirectional"))
    )
    (net (code "69") (name "/IO22") (class "Default")
      (node (ref "23_22") (pin "2") (pinfunction "2_2") (pintype "bidirectional"))
      (node (ref "U$6") (pin "2") (pinfunction "2_2") (pintype "bidirectional"))
      (node (ref "U1") (pin "36") (pinfunction "IO22_36") (pintype "bidirectional"))
    )
    (net (code "70") (name "/IO23") (class "Default")
      (node (ref "23_22") (pin "1") (pinfunction "1_1") (pintype "bidirectional"))
      (node (ref "U$6") (pin "1") (pinfunction "1_1") (pintype "bidirectional"))
      (node (ref "U1") (pin "37") (pinfunction "IO23_37") (pintype "bidirectional"))
    )
    (net (code "71") (name "/IO25") (class "Default")
      (node (ref "32_33_25_26_27_14_12_GND_13") (pin "3") (pinfunction "3_3") (pintype "bidirectional"))
      (node (ref "U$4") (pin "3") (pinfunction "3_3") (pintype "bidirectional"))
      (node (ref "U1") (pin "9") (pinfunction "IO25_9") (pintype "bidirectional"))
    )
    (net (code "72") (name "/IO26") (class "Default")
      (node (ref "32_33_25_26_27_14_12_GND_13") (pin "4") (pinfunction "4_4") (pintype "bidirectional"))
      (node (ref "U$4") (pin "4") (pinfunction "4_4") (pintype "bidirectional"))
      (node (ref "U1") (pin "10") (pinfunction "IO26_10") (pintype "bidirectional"))
    )
    (net (code "73") (name "/IO27") (class "Default")
      (node (ref "32_33_25_26_27_14_12_GND_13") (pin "5") (pinfunction "5_5") (pintype "bidirectional"))
      (node (ref "U$4") (pin "5") (pinfunction "5_5") (pintype "bidirectional"))
      (node (ref "U1") (pin "11") (pinfunction "IO27_11") (pintype "bidirectional"))
    )
    (net (code "74") (name "/IO32") (class "Default")
      (node (ref "32_33_25_26_27_14_12_GND_13") (pin "1") (pinfunction "1_1") (pintype "bidirectional"))
      (node (ref "U$4") (pin "1") (pinfunction "1_1") (pintype "bidirectional"))
      (node (ref "U1") (pin "7") (pinfunction "IO32_7") (pintype "bidirectional"))
    )
    (net (code "75") (name "/IO33") (class "Default")
      (node (ref "32_33_25_26_27_14_12_GND_13") (pin "2") (pinfunction "2_2") (pintype "bidirectional"))
      (node (ref "U$4") (pin "2") (pinfunction "2_2") (pintype "bidirectional"))
      (node (ref "U1") (pin "8") (pinfunction "IO33_8") (pintype "bidirectional"))
    )
    (net (code "76") (name "/IO34") (class "Default")
      (node (ref "R2_220Ω") (pin "1") (pinfunction "1_1") (pintype "passive"))
      (node (ref "U1") (pin "5") (pinfunction "IO34_5") (pintype "bidirectional"))
    )
    (net (code "77") (name "/IO35") (class "Default")
      (node (ref "R1_220Ω") (pin "1") (pinfunction "1_1") (pintype "passive"))
      (node (ref "U1") (pin "6") (pinfunction "IO35_6") (pintype "bidirectional"))
    )
    (net (code "78") (name "/PA0") (class "Default")
      (node (ref "U$2") (pin "P$36") (pinfunction "PA0_P$36") (pintype "bidirectional"))
      (node (ref "U$30") (pin "5") (pinfunction "5_5") (pintype "bidirectional"))
      (node (ref "VBAT_PC13_PC14_PC15_PA0_PA1") (pin "5") (pinfunction "5_5") (pintype "bidirectional"))
    )
    (net (code "79") (name "/PA1") (class "Default")
      (node (ref "U$2") (pin "P$35") (pinfunction "PA1_P$35") (pintype "bidirectional"))
      (node (ref "U$30") (pin "6") (pinfunction "6_6") (pintype "bidirectional"))
      (node (ref "VBAT_PC13_PC14_PC15_PA0_PA1") (pin "6") (pinfunction "6_6") (pintype "bidirectional"))
    )
    (net (code "80") (name "/PA2") (class "Default")
      (node (ref "GND_PA3_PA2") (pin "3") (pinfunction "3_3") (pintype "bidirectional"))
      (node (ref "U$2") (pin "P$34") (pinfunction "PA2_P$34") (pintype "bidirectional"))
    )
    (net (code "81") (name "/PA3") (class "Default")
      (node (ref "GND_PA3_PA2") (pin "2") (pinfunction "2_2") (pintype "bidirectional"))
      (node (ref "U$2") (pin "P$33") (pinfunction "PA3_P$33") (pintype "bidirectional"))
    )
    (net (code "82") (name "/PA4") (class "Default")
      (node (ref "5V_GND1") (pin "1") (pinfunction "1_1") (pintype "bidirectional"))
      (node (ref "PA4_PA5_PA6_PA7") (pin "1") (pinfunction "1_1") (pintype "bidirectional"))
      (node (ref "U$2") (pin "P$32") (pinfunction "PA4_P$32") (pintype "bidirectional"))
    )
    (net (code "83") (name "/PA5") (class "Default")
      (node (ref "5V_GND1") (pin "2") (pinfunction "2_2") (pintype "bidirectional"))
      (node (ref "PA4_PA5_PA6_PA7") (pin "2") (pinfunction "2_2") (pintype "bidirectional"))
      (node (ref "U$2") (pin "P$31") (pinfunction "PA5_P$31") (pintype "bidirectional"))
    )
    (net (code "84") (name "/PA6") (class "Default")
      (node (ref "5V_GND1") (pin "3") (pinfunction "3_3") (pintype "bidirectional"))
      (node (ref "PA4_PA5_PA6_PA7") (pin "3") (pinfunction "3_3") (pintype "bidirectional"))
      (node (ref "U$2") (pin "P$30") (pinfunction "PA6_P$30") (pintype "bidirectional"))
    )
    (net (code "85") (name "/PA7") (class "Default")
      (node (ref "5V_GND1") (pin "4") (pinfunction "4_4") (pintype "bidirectional"))
      (node (ref "PA4_PA5_PA6_PA7") (pin "4") (pinfunction "4_4") (pintype "bidirectional"))
      (node (ref "U$2") (pin "P$29") (pinfunction "PA7_P$29") (pintype "bidirectional"))
    )
    (net (code "86") (name "/PA8") (class "Default")
      (node (ref "PA9_PA8_GND_5V") (pin "3") (pinfunction "3_3") (pintype "bidirectional"))
      (node (ref "U$2") (pin "P$5") (pinfunction "PA8_P$5") (pintype "bidirectional"))
    )
    (net (code "87") (name "/PA9") (class "Default")
      (node (ref "PA9_PA8_GND_5V") (pin "4") (pinfunction "4_4") (pintype "bidirectional"))
      (node (ref "U$2") (pin "P$6") (pinfunction "PA9_P$6") (pintype "bidirectional"))
    )
    (net (code "88") (name "/PA10") (class "Default")
      (node (ref "PA10_PA11_GND_5V") (pin "4") (pinfunction "4_4") (pintype "bidirectional"))
      (node (ref "U$2") (pin "P$7") (pinfunction "PA10_P$7") (pintype "bidirectional"))
    )
    (net (code "89") (name "/PA11") (class "Default")
      (node (ref "PA10_PA11_GND_5V") (pin "3") (pinfunction "3_3") (pintype "bidirectional"))
      (node (ref "U$2") (pin "P$8") (pinfunction "PA11_P$8") (pintype "bidirectional"))
    )
    (net (code "90") (name "/PA12") (class "Default")
      (node (ref "PA12_PA15_GND_5V") (pin "4") (pinfunction "4_4") (pintype "bidirectional"))
      (node (ref "U$2") (pin "P$9") (pinfunction "PA12_P$9") (pintype "bidirectional"))
    )
    (net (code "91") (name "/PA15") (class "Default")
      (node (ref "PA12_PA15_GND_5V") (pin "3") (pinfunction "3_3") (pintype "bidirectional"))
      (node (ref "U$2") (pin "P$10") (pinfunction "PA15_P$10") (pintype "bidirectional"))
    )
    (net (code "92") (name "/PB0") (class "Default")
      (node (ref "5V_GND_PB1_PB0") (pin "4") (pinfunction "4_4") (pintype "bidirectional"))
      (node (ref "U$2") (pin "P$28") (pinfunction "PB0_P$28") (pintype "bidirectional"))
    )
    (net (code "93") (name "/PB1") (class "Default")
      (node (ref "5V_GND_PB1_PB0") (pin "3") (pinfunction "3_3") (pintype "bidirectional"))
      (node (ref "U$2") (pin "P$27") (pinfunction "PB1_P$27") (pintype "bidirectional"))
    )
    (net (code "94") (name "/PB3") (class "Default")
      (node (ref "PB3_PB4_PB5_PB6_PB7_PB8_PB9") (pin "7") (pinfunction "7_7") (pintype "bidirectional"))
      (node (ref "U$2") (pin "P$11") (pinfunction "PB3_P$11") (pintype "bidirectional"))
      (node (ref "U$33") (pin "7") (pinfunction "7_7") (pintype "bidirectional"))
    )
    (net (code "95") (name "/PB4") (class "Default")
      (node (ref "PB3_PB4_PB5_PB6_PB7_PB8_PB9") (pin "6") (pinfunction "6_6") (pintype "bidirectional"))
      (node (ref "U$2") (pin "P$12") (pinfunction "PB4_P$12") (pintype "bidirectional"))
      (node (ref "U$33") (pin "6") (pinfunction "6_6") (pintype "bidirectional"))
    )
    (net (code "96") (name "/PB5") (class "Default")
      (node (ref "PB3_PB4_PB5_PB6_PB7_PB8_PB9") (pin "5") (pinfunction "5_5") (pintype "bidirectional"))
      (node (ref "U$2") (pin "P$13") (pinfunction "PB5_P$13") (pintype "bidirectional"))
      (node (ref "U$33") (pin "5") (pinfunction "5_5") (pintype "bidirectional"))
    )
    (net (code "97") (name "/PB6") (class "Default")
      (node (ref "PB3_PB4_PB5_PB6_PB7_PB8_PB9") (pin "4") (pinfunction "4_4") (pintype "bidirectional"))
      (node (ref "U$2") (pin "P$14") (pinfunction "PB6_P$14") (pintype "bidirectional"))
      (node (ref "U$33") (pin "4") (pinfunction "4_4") (pintype "bidirectional"))
    )
    (net (code "98") (name "/PB7") (class "Default")
      (node (ref "PB3_PB4_PB5_PB6_PB7_PB8_PB9") (pin "3") (pinfunction "3_3") (pintype "bidirectional"))
      (node (ref "U$2") (pin "P$15") (pinfunction "PB7_P$15") (pintype "bidirectional"))
      (node (ref "U$33") (pin "3") (pinfunction "3_3") (pintype "bidirectional"))
    )
    (net (code "99") (name "/PB8") (class "Default")
      (node (ref "PB3_PB4_PB5_PB6_PB7_PB8_PB9") (pin "2") (pinfunction "2_2") (pintype "bidirectional"))
      (node (ref "U$2") (pin "P$16") (pinfunction "PB8_P$16") (pintype "bidirectional"))
      (node (ref "U$33") (pin "2") (pinfunction "2_2") (pintype "bidirectional"))
    )
    (net (code "100") (name "/PB9") (class "Default")
      (node (ref "PB3_PB4_PB5_PB6_PB7_PB8_PB9") (pin "1") (pinfunction "1_1") (pintype "bidirectional"))
      (node (ref "U$2") (pin "P$17") (pinfunction "PB9_P$17") (pintype "bidirectional"))
      (node (ref "U$33") (pin "1") (pinfunction "1_1") (pintype "bidirectional"))
    )
    (net (code "101") (name "/PB10") (class "Default")
      (node (ref "PB10_PB11_RST_3V3_GND") (pin "1") (pinfunction "1_1") (pintype "bidirectional"))
      (node (ref "U$2") (pin "P$26") (pinfunction "PB10_P$26") (pintype "bidirectional"))
      (node (ref "U$26") (pin "1") (pinfunction "1_1") (pintype "bidirectional"))
    )
    (net (code "102") (name "/PB11") (class "Default")
      (node (ref "PB10_PB11_RST_3V3_GND") (pin "2") (pinfunction "2_2") (pintype "bidirectional"))
      (node (ref "U$2") (pin "P$25") (pinfunction "PB11_P$25") (pintype "bidirectional"))
      (node (ref "U$26") (pin "2") (pinfunction "2_2") (pintype "bidirectional"))
    )
    (net (code "103") (name "/PB12") (class "Default")
      (node (ref "PB12_PB13_PB14_PB15") (pin "4") (pinfunction "4_4") (pintype "bidirectional"))
      (node (ref "U$2") (pin "P$1") (pinfunction "PB12_P$1") (pintype "bidirectional"))
      (node (ref "U$35") (pin "4") (pinfunction "4_4") (pintype "bidirectional"))
    )
    (net (code "104") (name "/PB13") (class "Default")
      (node (ref "PB12_PB13_PB14_PB15") (pin "3") (pinfunction "3_3") (pintype "bidirectional"))
      (node (ref "U$2") (pin "P$2") (pinfunction "PB13_P$2") (pintype "bidirectional"))
      (node (ref "U$35") (pin "3") (pinfunction "3_3") (pintype "bidirectional"))
    )
    (net (code "105") (name "/PB14") (class "Default")
      (node (ref "PB12_PB13_PB14_PB15") (pin "2") (pinfunction "2_2") (pintype "bidirectional"))
      (node (ref "U$2") (pin "P$3") (pinfunction "PB14_P$3") (pintype "bidirectional"))
      (node (ref "U$35") (pin "2") (pinfunction "2_2") (pintype "bidirectional"))
    )
    (net (code "106") (name "/PB15") (class "Default")
      (node (ref "PB12_PB13_PB14_PB15") (pin "1") (pinfunction "1_1") (pintype "bidirectional"))
      (node (ref "U$2") (pin "P$4") (pinfunction "PB15_P$4") (pintype "bidirectional"))
      (node (ref "U$35") (pin "1") (pinfunction "1_1") (pintype "bidirectional"))
    )
    (net (code "107") (name "/PC13") (class "Default")
      (node (ref "U$2") (pin "P$39") (pinfunction "PC13_P$39") (pintype "bidirectional"))
      (node (ref "U$30") (pin "2") (pinfunction "2_2") (pintype "bidirectional"))
      (node (ref "VBAT_PC13_PC14_PC15_PA0_PA1") (pin "2") (pinfunction "2_2") (pintype "bidirectional"))
    )
    (net (code "108") (name "/PC14") (class "Default")
      (node (ref "U$2") (pin "P$38") (pinfunction "PC14_P$38") (pintype "bidirectional"))
      (node (ref "U$30") (pin "3") (pinfunction "3_3") (pintype "bidirectional"))
      (node (ref "VBAT_PC13_PC14_PC15_PA0_PA1") (pin "3") (pinfunction "3_3") (pintype "bidirectional"))
    )
    (net (code "109") (name "/PC15") (class "Default")
      (node (ref "U$2") (pin "P$37") (pinfunction "PC15_P$37") (pintype "bidirectional"))
      (node (ref "U$30") (pin "4") (pinfunction "4_4") (pintype "bidirectional"))
      (node (ref "VBAT_PC13_PC14_PC15_PA0_PA1") (pin "4") (pinfunction "4_4") (pintype "bidirectional"))
    )
    (net (code "110") (name "/RST") (class "Default")
      (node (ref "RST_3V3_GND") (pin "1") (pinfunction "1_1") (pintype "bidirectional"))
      (node (ref "U$1") (pin "P$24") (pinfunction "RESET_P$24") (pintype "bidirectional"))
      (node (ref "U$24") (pin "1") (pinfunction "1_1") (pintype "bidirectional"))
    )
    (net (code "111") (name "/RST1") (class "Default")
      (node (ref "PB10_PB11_RST_3V3_GND") (pin "3") (pinfunction "3_3") (pintype "bidirectional"))
      (node (ref "U$2") (pin "P$24") (pinfunction "RESET_P$24") (pintype "bidirectional"))
      (node (ref "U$26") (pin "3") (pinfunction "3_3") (pintype "bidirectional"))
    )
    (net (code "112") (name "/RX") (class "Default")
      (node (ref "TX_RX_GND") (pin "2") (pinfunction "2_2") (pintype "bidirectional"))
      (node (ref "U1") (pin "34") (pinfunction "RXD0_34") (pintype "input"))
    )
    (net (code "113") (name "/TX") (class "Default")
      (node (ref "TX_RX_GND") (pin "3") (pinfunction "3_3") (pintype "bidirectional"))
      (node (ref "U1") (pin "35") (pinfunction "TXD0_35") (pintype "output"))
    )
    (net (code "114") (name "/VBAT") (class "Default")
      (node (ref "U$1") (pin "P$40") (pinfunction "VBAT_P$40") (pintype "bidirectional"))
      (node (ref "U$18") (pin "1") (pinfunction "1_1") (pintype "bidirectional"))
      (node (ref "VBAT_C13_C14_C15") (pin "1") (pinfunction "1_1") (pintype "bidirectional"))
    )
    (net (code "115") (name "/VBAT1") (class "Default")
      (node (ref "U$2") (pin "P$40") (pinfunction "VBAT_P$40") (pintype "bidirectional"))
      (node (ref "U$30") (pin "1") (pinfunction "1_1") (pintype "bidirectional"))
      (node (ref "VBAT_PC13_PC14_PC15_PA0_PA1") (pin "1") (pinfunction "1_1") (pintype "bidirectional"))
    )
    (net (code "116") (name "/VN") (class "Default")
      (node (ref "3V3_EN_VP_VN") (pin "4") (pinfunction "4_4") (pintype "passive"))
      (node (ref "JP2") (pin "4") (pinfunction "4_4") (pintype "passive"))
      (node (ref "U1") (pin "4") (pinfunction "SENSOR_VN_4") (pintype "input"))
    )
    (net (code "117") (name "/VP") (class "Default")
      (node (ref "3V3_EN_VP_VN") (pin "3") (pinfunction "3_3") (pintype "passive"))
      (node (ref "JP2") (pin "3") (pinfunction "3_3") (pintype "passive"))
      (node (ref "U1") (pin "3") (pinfunction "SENSOR_VP_3") (pintype "input"))
    )
    (net (code "118") (name "GND") (class "Default")
      (node (ref "17_16_GND") (pin "1") (pinfunction "1_1") (pintype "bidirectional"))
      (node (ref "5V_GND") (pin "1") (pinfunction "1_1") (pintype "bidirectional"))
      (node (ref "GND_D2_D3") (pin "1") (pinfunction "1_1") (pintype "bidirectional"))
      (node (ref "GND_VCC") (pin "C") (pinfunction "C_C") (pintype "passive"))
      (node (ref "GND_VCC1") (pin "C") (pinfunction "C_C") (pintype "passive"))
      (node (ref "TX_RX_GND") (pin "1") (pinfunction "1_1") (pintype "bidirectional"))
      (node (ref "U1") (pin "38") (pinfunction "GND3_38") (pintype "power_in"))
    )
    (net (code "119") (name "Net-(5V_5V-Pad1)") (class "Default")
      (node (ref "5V_5V") (pin "1") (pinfunction "1_1") (pintype "passive"))
      (node (ref "D2") (pin "A") (pinfunction "A_A") (pintype "passive"))
    )
    (net (code "120") (name "Net-(5V_5V-Pad2)") (class "Default")
      (node (ref "5V_5V") (pin "2") (pinfunction "2_2") (pintype "passive"))
      (node (ref "5V_GND") (pin "2") (pinfunction "2_2") (pintype "bidirectional"))
    )
    (net (code "121") (name "Net-(5V_5V1-Pad1)") (class "Default")
      (node (ref "5V_5V1") (pin "1") (pinfunction "1_1") (pintype "passive"))
      (node (ref "D1") (pin "A") (pinfunction "A_A") (pintype "passive"))
    )
    (net (code "122") (name "Net-(5V_5V1-Pad2)") (class "Default")
      (node (ref "5V_5V1") (pin "2") (pinfunction "2_2") (pintype "passive"))
      (node (ref "GND_5V") (pin "2") (pinfunction "2_2") (pintype "bidirectional"))
    )
    (net (code "123") (name "Net-(5V_5V2-Pad1)") (class "Default")
      (node (ref "5V_5V2") (pin "1") (pinfunction "1_1") (pintype "passive"))
      (node (ref "D3") (pin "A") (pinfunction "A_A") (pintype "passive"))
    )
    (net (code "124") (name "Net-(5V_5V2-Pad2)") (class "Default")
      (node (ref "5V_5V2") (pin "2") (pinfunction "2_2") (pintype "passive"))
      (node (ref "J5") (pin "2") (pinfunction "2_2") (pintype "bidirectional"))
    )
    (net (code "125") (name "Net-(GND_VCC-PadA)") (class "Default")
      (node (ref "GND_VCC") (pin "A") (pinfunction "A_A") (pintype "passive"))
      (node (ref "R1_220Ω") (pin "2") (pinfunction "2_2") (pintype "passive"))
    )
    (net (code "126") (name "Net-(GND_VCC1-PadA)") (class "Default")
      (node (ref "GND_VCC1") (pin "A") (pinfunction "A_A") (pintype "passive"))
      (node (ref "R2_220Ω") (pin "2") (pinfunction "2_2") (pintype "passive"))
    )
    (net (code "127") (name "unconnected-(5V_5V-Pad3)") (class "Default")
      (node (ref "5V_5V") (pin "3") (pinfunction "3_3") (pintype "passive"))
    )
    (net (code "128") (name "unconnected-(5V_5V1-Pad3)") (class "Default")
      (node (ref "5V_5V1") (pin "3") (pinfunction "3_3") (pintype "passive"))
    )
    (net (code "129") (name "unconnected-(5V_5V2-Pad3)") (class "Default")
      (node (ref "5V_5V2") (pin "3") (pinfunction "3_3") (pintype "passive"))
    )
  )
)
